# Copy_of_2019-07-31_19-54-381.net
KiCad netlist of a schematic drawn in Altium Designer
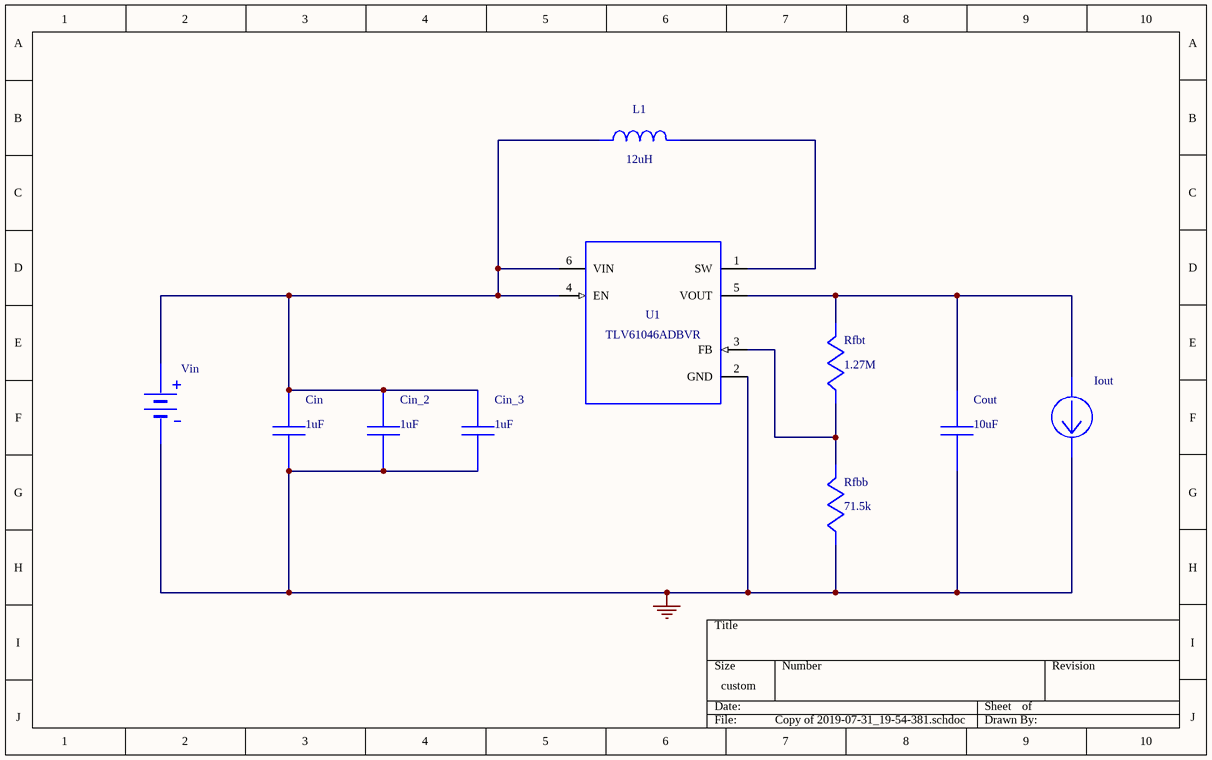
[diagram p0: Copy of 2019-07-31_19-54-381.schdoc]

(export (version "E")
  (design (tool "Eeschema 10.0.6"))
  (components
    (comp (ref "Cin")
      (value "1uF")
      (description "C0603C105K8PACTU")
      (libsource (lib "TI WEBENCH") (part "Cin"))
    )
    (comp (ref "Cin_2")
      (value "1uF")
      (description "C0603C105K8PACTU")
      (libsource (lib "TI WEBENCH") (part "Cin_2"))
    )
    (comp (ref "Cin_3")
      (value "1uF")
      (description "C0603C105K8PACTU")
      (libsource (lib "TI WEBENCH") (part "Cin_3"))
    )
    (comp (ref "Cout")
      (value "10uF")
      (description "CL32B106KBJNNWE")
      (libsource (lib "TI WEBENCH") (part "Cout"))
    )
    (comp (ref "Iout") (value "WB_CURRENT_LOAD") (libsource (lib "TI WEBENCH") (part "Iout")))
    (comp (ref "L1") (value "12uH") (description "NPI43C120MTRF") (libsource (lib "TI WEBENCH") (part "L1")))
    (comp (ref "Rfbb")
      (value "71.5k")
      (description "CRCW040271K5FKED")
      (libsource (lib "TI WEBENCH") (part "Rfbb"))
    )
    (comp (ref "Rfbt")
      (value "1.27M")
      (description "CRCW04021M27FKED")
      (libsource (lib "TI WEBENCH") (part "Rfbt"))
    )
    (comp (ref "U1")
      (value "TLV61046ADBVR")
      (fields (field (name "PACKAGEREFERENCE") "TLV61046ADBVR"))
      (libsource (lib "TI WEBENCH") (part "U1"))
    )
    (comp (ref "Vin") (value "WB_BATTERY") (libsource (lib "TI WEBENCH") (part "Vin")))
  )
  (nets
    (net (code "1") (name "0") (class "Default")
      (node (ref "Cin") (pin "2") (pinfunction "2_2") (pintype "passive"))
      (node (ref "Cin_2") (pin "2") (pinfunction "2_2") (pintype "passive"))
      (node (ref "Cin_3") (pin "2") (pinfunction "2_2") (pintype "passive"))
      (node (ref "Cout") (pin "2") (pinfunction "2_2") (pintype "passive"))
      (node (ref "Iout") (pin "2") (pinfunction "-_2") (pintype "passive"))
      (node (ref "Rfbb") (pin "2") (pinfunction "2_2") (pintype "passive"))
      (node (ref "U1") (pin "2") (pinfunction "GND_2") (pintype "power_in"))
      (node (ref "Vin") (pin "2") (pinfunction "-_2") (pintype "passive"))
    )
    (net (code "2") (name "Net-(Iout-+)") (class "Default")
      (node (ref "Cout") (pin "1") (pinfunction "1_1") (pintype "passive"))
      (node (ref "Iout") (pin "1") (pinfunction "+_1") (pintype "passive"))
      (node (ref "Rfbt") (pin "1") (pinfunction "1_1") (pintype "passive"))
      (node (ref "U1") (pin "5") (pinfunction "VOUT_5") (pintype "power_in"))
    )
    (net (code "3") (name "Net-(U1-EN)") (class "Default")
      (node (ref "Cin") (pin "1") (pinfunction "1_1") (pintype "passive"))
      (node (ref "Cin_2") (pin "1") (pinfunction "1_1") (pintype "passive"))
      (node (ref "Cin_3") (pin "1") (pinfunction "1_1") (pintype "passive"))
      (node (ref "L1") (pin "1") (pinfunction "1_1") (pintype "passive"))
      (node (ref "U1") (pin "4") (pinfunction "EN_4") (pintype "input"))
      (node (ref "U1") (pin "6") (pinfunction "VIN_6") (pintype "power_in"))
      (node (ref "Vin") (pin "1") (pinfunction "+_1") (pintype "passive"))
    )
    (net (code "4") (name "Net-(U1-FB)") (class "Default")
      (node (ref "Rfbb") (pin "1") (pinfunction "1_1") (pintype "passive"))
      (node (ref "Rfbt") (pin "2") (pinfunction "2_2") (pintype "passive"))
      (node (ref "U1") (pin "3") (pinfunction "FB_3") (pintype "input"))
    )
    (net (code "5") (name "Net-(U1-SW)") (class "Default")
      (node (ref "L1") (pin "2") (pinfunction "2_2") (pintype "passive"))
      (node (ref "U1") (pin "1") (pinfunction "SW_1") (pintype "power_in"))
    )
  )
)
